# Placa_final_para_testes.net
KiCad netlist of a schematic drawn in EAGLE
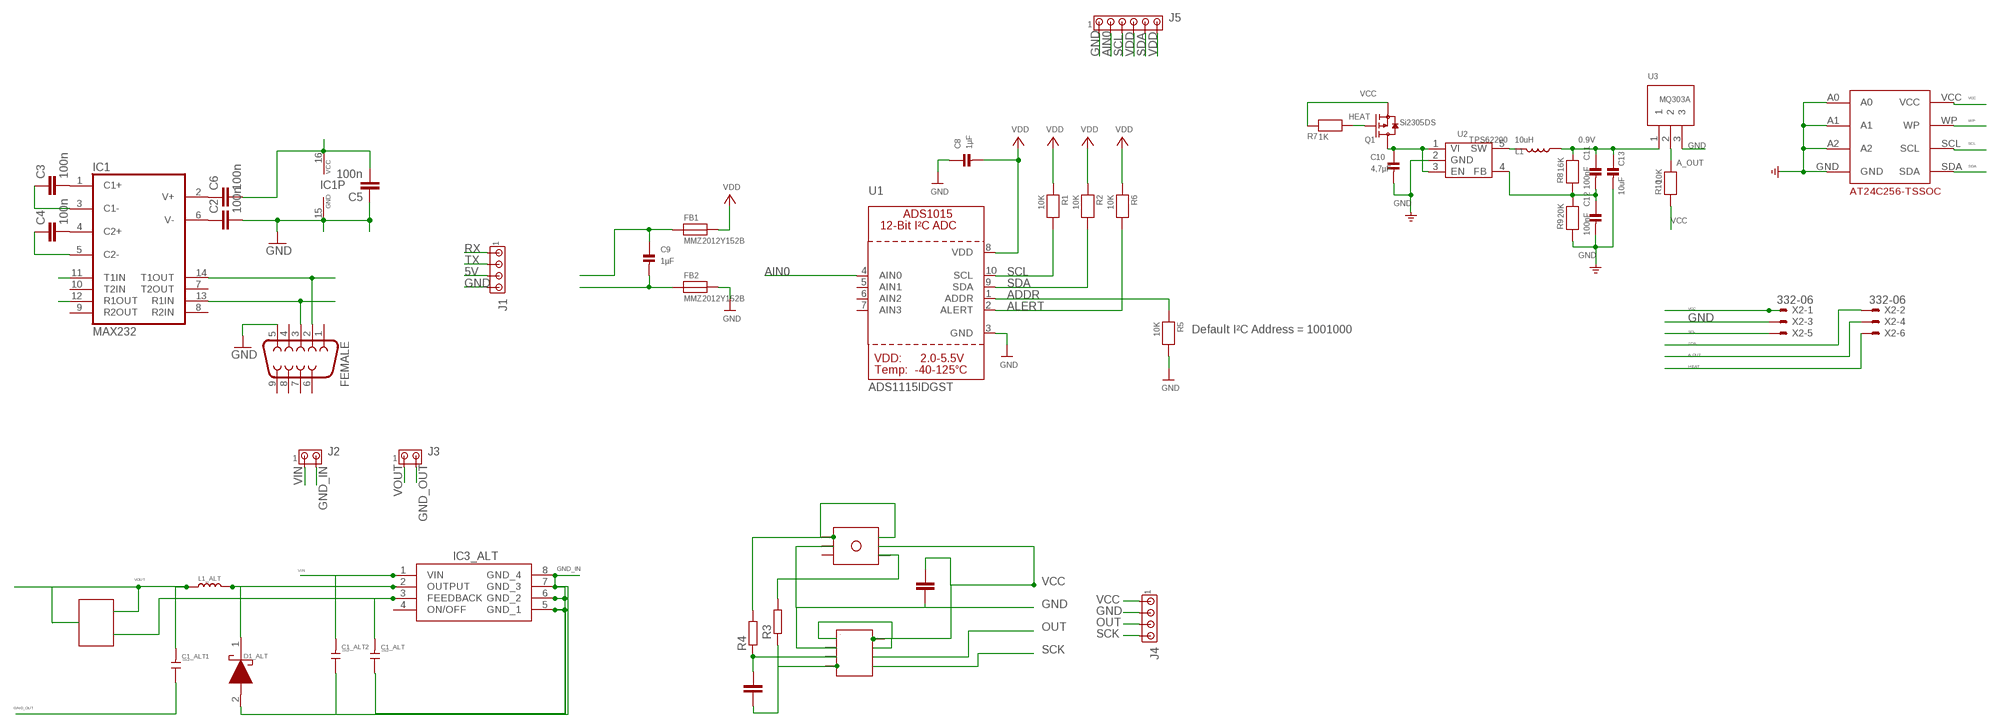
[diagram p0: schematic, sheet 1]

(export (version "E")
  (design (tool "Eeschema 10.0.6"))
  (components
    (comp (ref "C1")
      (value "100n")
      (footprint "eagle-import:C0805")
      (libsource (lib "eagle-import") (part "C-EUC0805"))
    )
    (comp (ref "C1_ALT")
      (value "105uF")
      (footprint "eagle-import:C0805")
      (libsource (lib "eagle-import") (part "C-0805"))
    )
    (comp (ref "C1_ALT1")
      (value "105uF")
      (footprint "eagle-import:C0805")
      (libsource (lib "eagle-import") (part "C-0805"))
    )
    (comp (ref "C1_ALT2")
      (value "105uF")
      (footprint "eagle-import:C0805")
      (libsource (lib "eagle-import") (part "C-0805"))
    )
    (comp (ref "C2")
      (value "100n")
      (footprint "eagle-import:C0805")
      (libsource (lib "eagle-import") (part "C-EUC0805"))
    )
    (comp (ref "C3")
      (value "100n")
      (footprint "eagle-import:C0805")
      (libsource (lib "eagle-import") (part "C-EUC0805"))
    )
    (comp (ref "C4")
      (value "100n")
      (footprint "eagle-import:C0805")
      (libsource (lib "eagle-import") (part "C-EUC0805"))
    )
    (comp (ref "C5")
      (value "100n")
      (footprint "eagle-import:C0805")
      (libsource (lib "eagle-import") (part "C-EUC0805"))
    )
    (comp (ref "C6")
      (value "100n")
      (footprint "eagle-import:C0805")
      (libsource (lib "eagle-import") (part "C-EUC0805"))
    )
    (comp (ref "C7")
      (value "100n")
      (footprint "eagle-import:C0805")
      (libsource (lib "eagle-import") (part "C-EUC0805"))
    )
    (comp (ref "C8")
      (value "1µF")
      (footprint "eagle-import:0805")
      (libsource (lib "eagle-import") (part "CAP_CERAMIC0805"))
    )
    (comp (ref "C9")
      (value "1µF")
      (footprint "eagle-import:0805")
      (libsource (lib "eagle-import") (part "CAP_CERAMIC0805"))
    )
    (comp (ref "C10")
      (value "4,7µF")
      (footprint "eagle-import:0805")
      (libsource (lib "eagle-import") (part "CAP_CERAMIC0805"))
    )
    (comp (ref "C11")
      (value "100nF")
      (footprint "eagle-import:0805")
      (libsource (lib "eagle-import") (part "CAP_CERAMIC0805"))
    )
    (comp (ref "C12")
      (value "100nF")
      (footprint "eagle-import:0805")
      (libsource (lib "eagle-import") (part "CAP_CERAMIC0805"))
    )
    (comp (ref "C13")
      (value "10uF")
      (footprint "eagle-import:0805")
      (libsource (lib "eagle-import") (part "CAP_CERAMIC0805"))
    )
    (comp (ref "D1_ALT")
      (value "1N5819HW1-7-F")
      (footprint "eagle-import:SODFL3518X115N")
      (fields (field (name "MOUSER_PART_NUMBER") "621-1N5819HW1-7-F"))
      (libsource (lib "eagle-import") (part "1N5819HW1-7-F"))
    )
    (comp (ref "FB1")
      (value "MMZ2012Y152B")
      (footprint "eagle-import:0805")
      (libsource (lib "eagle-import") (part "FERRITE0805"))
    )
    (comp (ref "FB2")
      (value "MMZ2012Y152B")
      (footprint "eagle-import:0805")
      (libsource (lib "eagle-import") (part "FERRITE0805"))
    )
    (comp (ref "FEMALE")
      (value "F09H")
      (footprint "eagle-import:F09H")
      (libsource (lib "eagle-import") (part "F09H"))
    )
    (comp (ref "IC1")
      (value "MAX232")
      (footprint "eagle-import:SO16")
      (libsource (lib "eagle-import") (part "MAX232ECWES"))
    )
    (comp (ref "IC3_ALT")
      (value "XL1509-3.3E1")
      (footprint "eagle-import:SOIC127P600X175-8N")
      (libsource (lib "eagle-import") (part "XL1509-3.3E1"))
    )
    (comp (ref "J1")
      (value "MTA04-156")
      (footprint "eagle-import:1X4MTA")
      (libsource (lib "eagle-import") (part "MTA04-156"))
    )
    (comp (ref "J2")
      (value "MTA02-156")
      (footprint "eagle-import:1X2MTA")
      (libsource (lib "eagle-import") (part "MTA02-156"))
    )
    (comp (ref "J3")
      (value "MTA02-156")
      (footprint "eagle-import:1X2MTA")
      (libsource (lib "eagle-import") (part "MTA02-156"))
    )
    (comp (ref "J4")
      (value "MTA04-100")
      (footprint "eagle-import:10X04MTA")
      (libsource (lib "eagle-import") (part "MTA04-100"))
    )
    (comp (ref "J5")
      (value "MTA06-156")
      (footprint "eagle-import:1X6MTA")
      (libsource (lib "eagle-import") (part "MTA06-156"))
    )
    (comp (ref "L1")
      (value "10uH")
      (footprint "eagle-import:PIO73")
      (libsource (lib "eagle-import") (part "L'PIO73'"))
    )
    (comp (ref "L1_ALT")
      (value "47uH")
      (footprint "eagle-import:PIO73")
      (libsource (lib "eagle-import") (part "discrete_211_L'PIO73'"))
    )
    (comp (ref "Q1")
      (value "Si2305DS")
      (footprint "eagle-import:SOT23")
      (libsource (lib "eagle-import") (part "MOSFET-P'SI2323CDS/SI2305DS{lt}BR{gt}'"))
    )
    (comp (ref "R1")
      (value "10K")
      (footprint "eagle-import:0805")
      (libsource (lib "eagle-import") (part "RESISTOR0805"))
    )
    (comp (ref "R2")
      (value "10K")
      (footprint "eagle-import:0805")
      (libsource (lib "eagle-import") (part "RESISTOR0805"))
    )
    (comp (ref "R3")
      (value "R-EU_R0805")
      (footprint "eagle-import:R0805")
      (libsource (lib "eagle-import") (part "R-EU_R0805"))
    )
    (comp (ref "R4")
      (value "R-EU_R0805")
      (footprint "eagle-import:R0805")
      (libsource (lib "eagle-import") (part "R-EU_R0805"))
    )
    (comp (ref "R5")
      (value "10K")
      (footprint "eagle-import:0805")
      (libsource (lib "eagle-import") (part "RESISTOR0805"))
    )
    (comp (ref "R6")
      (value "10K")
      (footprint "eagle-import:0805")
      (libsource (lib "eagle-import") (part "RESISTOR0805"))
    )
    (comp (ref "R7")
      (value "1K")
      (footprint "eagle-import:0805")
      (libsource (lib "eagle-import") (part "RESISTOR0805"))
    )
    (comp (ref "R8")
      (value "16K")
      (footprint "eagle-import:0805")
      (libsource (lib "eagle-import") (part "RESISTOR0805"))
    )
    (comp (ref "R9")
      (value "20K")
      (footprint "eagle-import:0805")
      (libsource (lib "eagle-import") (part "RESISTOR0805"))
    )
    (comp (ref "R10")
      (value "10K")
      (footprint "eagle-import:0805")
      (libsource (lib "eagle-import") (part "RESISTOR0805"))
    )
    (comp (ref "U$1")
      (value "TRIMPOT")
      (footprint "eagle-import:TRIMPOT")
      (libsource (lib "eagle-import") (part "TRIMPOT"))
    )
    (comp (ref "U$2")
      (value "HX710B")
      (footprint "eagle-import:HX710B")
      (libsource (lib "eagle-import") (part "HX710B"))
    )
    (comp (ref "U$3")
      (value "PRESSURE")
      (footprint "eagle-import:PRESSURE")
      (libsource (lib "eagle-import") (part "PRESSURE"))
    )
    (comp (ref "U$15")
      (value "DECADE-AT24C256-10TI-2.7")
      (footprint "eagle-import:DECADE-AT24CXX")
      (libsource (lib "eagle-import") (part "DECADE-AT24C256-10TI-2.7"))
    )
    (comp (ref "U1")
      (value "ADS1115IDGST")
      (footprint "eagle-import:MSOP10")
      (libsource (lib "eagle-import") (part "ADC_ADS1015"))
    )
    (comp (ref "U2")
      (value "TPS62200")
      (footprint "eagle-import:SOT23-5")
      (libsource (lib "eagle-import") (part "TPS62200DBV"))
    )
    (comp (ref "U3")
      (value "MQ303A")
      (footprint "eagle-import:MQ303A")
      (libsource (lib "eagle-import") (part "MQ303A"))
    )
    (comp (ref "X2")
      (value "332-06")
      (footprint "eagle-import:332-06")
      (libsource (lib "eagle-import") (part "332-06"))
    )
  )
  (nets
    (net (code "1") (name "/0.9V") (class "Default")
      (node (ref "C11") (pin "1") (pinfunction "P$1_1") (pintype "passive"))
      (node (ref "C13") (pin "1") (pinfunction "P$1_1") (pintype "passive"))
      (node (ref "L1") (pin "2") (pinfunction "2_2") (pintype "passive"))
      (node (ref "R8") (pin "2") (pinfunction "2_2") (pintype "passive"))
      (node (ref "U3") (pin "1") (pinfunction "1_1") (pintype "bidirectional"))
    )
    (net (code "2") (name "/5V") (class "Default")
      (node (ref "C5") (pin "2") (pinfunction "2_2") (pintype "passive"))
      (node (ref "C6") (pin "2") (pinfunction "2_2") (pintype "passive"))
      (node (ref "IC1") (pin "16") (pinfunction "VCC_16") (pintype "power_in"))
      (node (ref "J1") (pin "3") (pinfunction "3_3") (pintype "passive"))
    )
    (net (code "3") (name "/ADDR") (class "Default")
      (node (ref "R5") (pin "1") (pinfunction "1_1") (pintype "passive"))
      (node (ref "U1") (pin "1") (pinfunction "ADDR_1") (pintype "bidirectional"))
    )
    (net (code "4") (name "/AIN0") (class "Default")
      (node (ref "J5") (pin "2") (pinfunction "2_2") (pintype "passive"))
      (node (ref "U1") (pin "4") (pinfunction "AIN0_4") (pintype "bidirectional"))
    )
    (net (code "5") (name "/ALERT") (class "Default")
      (node (ref "R6") (pin "2") (pinfunction "2_2") (pintype "passive"))
      (node (ref "U1") (pin "2") (pinfunction "ALERT_2") (pintype "bidirectional"))
    )
    (net (code "6") (name "/A_OUT") (class "Default")
      (node (ref "R10") (pin "2") (pinfunction "2_2") (pintype "passive"))
      (node (ref "U3") (pin "2") (pinfunction "2_2") (pintype "bidirectional"))
      (node (ref "X2") (pin "4") (pinfunction "S_4") (pintype "passive"))
    )
    (net (code "7") (name "/GND_IN") (class "Default")
      (node (ref "C1_ALT") (pin "1") (pinfunction "1_1") (pintype "passive"))
      (node (ref "C1_ALT2") (pin "1") (pinfunction "1_1") (pintype "passive"))
      (node (ref "D1_ALT") (pin "2") (pinfunction "A_2") (pintype "bidirectional"))
      (node (ref "IC3_ALT") (pin "5") (pinfunction "GND_1_5") (pintype "bidirectional"))
      (node (ref "IC3_ALT") (pin "6") (pinfunction "GND_2_6") (pintype "bidirectional"))
      (node (ref "IC3_ALT") (pin "7") (pinfunction "GND_3_7") (pintype "bidirectional"))
      (node (ref "IC3_ALT") (pin "8") (pinfunction "GND_4_8") (pintype "bidirectional"))
      (node (ref "J2") (pin "2") (pinfunction "2_2") (pintype "passive"))
    )
    (net (code "8") (name "/GND_OUT") (class "Default")
      (node (ref "C1_ALT1") (pin "1") (pinfunction "1_1") (pintype "passive"))
      (node (ref "J3") (pin "2") (pinfunction "2_2") (pintype "passive"))
    )
    (net (code "9") (name "/HEAT") (class "Default")
      (node (ref "Q1") (pin "1") (pinfunction "G_1") (pintype "passive"))
      (node (ref "R7") (pin "2") (pinfunction "2_2") (pintype "passive"))
      (node (ref "X2") (pin "6") (pinfunction "S_6") (pintype "passive"))
    )
    (net (code "10") (name "/OUT") (class "Default")
      (node (ref "J4") (pin "3") (pinfunction "3_3") (pintype "passive"))
      (node (ref "U$2") (pin "DOUT") (pinfunction "DOUT_DOUT") (pintype "bidirectional"))
    )
    (net (code "11") (name "/RX") (class "Default")
      (node (ref "IC1") (pin "12") (pinfunction "R1OUT_12") (pintype "output"))
      (node (ref "J1") (pin "1") (pinfunction "1_1") (pintype "passive"))
    )
    (net (code "12") (name "/SCK") (class "Default")
      (node (ref "J4") (pin "4") (pinfunction "4_4") (pintype "passive"))
      (node (ref "U$2") (pin "SCK") (pinfunction "SCK_SCK") (pintype "bidirectional"))
    )
    (net (code "13") (name "/SCL") (class "Default")
      (node (ref "J5") (pin "3") (pinfunction "3_3") (pintype "passive"))
      (node (ref "R1") (pin "2") (pinfunction "2_2") (pintype "passive"))
      (node (ref "U$15") (pin "SCL") (pinfunction "SCL_SCL") (pintype "bidirectional"))
      (node (ref "U1") (pin "10") (pinfunction "SCL_10") (pintype "bidirectional"))
      (node (ref "X2") (pin "5") (pinfunction "S_5") (pintype "passive"))
    )
    (net (code "14") (name "/SDA") (class "Default")
      (node (ref "J5") (pin "5") (pinfunction "5_5") (pintype "passive"))
      (node (ref "R2") (pin "2") (pinfunction "2_2") (pintype "passive"))
      (node (ref "U$15") (pin "SDA") (pinfunction "SDA_SDA") (pintype "bidirectional"))
      (node (ref "U1") (pin "9") (pinfunction "SDA_9") (pintype "bidirectional"))
      (node (ref "X2") (pin "2") (pinfunction "S_2") (pintype "passive"))
    )
    (net (code "15") (name "/TX") (class "Default")
      (node (ref "IC1") (pin "11") (pinfunction "T1IN_11") (pintype "input"))
      (node (ref "J1") (pin "2") (pinfunction "2_2") (pintype "passive"))
    )
    (net (code "16") (name "/VCC") (class "Default")
      (node (ref "C7") (pin "1") (pinfunction "1_1") (pintype "passive"))
      (node (ref "J4") (pin "1") (pinfunction "1_1") (pintype "passive"))
      (node (ref "Q1") (pin "2") (pinfunction "S_2") (pintype "passive"))
      (node (ref "R10") (pin "1") (pinfunction "1_1") (pintype "passive"))
      (node (ref "R7") (pin "1") (pinfunction "1_1") (pintype "passive"))
      (node (ref "U$15") (pin "VCC") (pinfunction "VCC_VCC") (pintype "bidirectional"))
      (node (ref "U$2") (pin "AVDD") (pinfunction "AVDD_AVDD") (pintype "bidirectional"))
      (node (ref "U$2") (pin "DVDD") (pinfunction "DVDD_DVDD") (pintype "bidirectional"))
      (node (ref "U$2") (pin "VREF") (pinfunction "VREF_VREF") (pintype "bidirectional"))
      (node (ref "U$3") (pin "5") (pinfunction "5_5") (pintype "bidirectional"))
      (node (ref "X2") (pin "1") (pinfunction "S_1") (pintype "passive"))
    )
    (net (code "17") (name "/VIN") (class "Default")
      (node (ref "C1_ALT2") (pin "2") (pinfunction "2_2") (pintype "passive"))
      (node (ref "IC3_ALT") (pin "1") (pinfunction "VIN_1") (pintype "bidirectional"))
      (node (ref "J2") (pin "1") (pinfunction "1_1") (pintype "passive"))
    )
    (net (code "18") (name "/VOUT") (class "Default")
      (node (ref "C1_ALT1") (pin "2") (pinfunction "2_2") (pintype "passive"))
      (node (ref "J3") (pin "1") (pinfunction "1_1") (pintype "passive"))
      (node (ref "L1_ALT") (pin "2") (pinfunction "2_2") (pintype "passive"))
      (node (ref "U$1") (pin "VCC1") (pinfunction "VCC1_VCC1") (pintype "bidirectional"))
      (node (ref "U$1") (pin "VCC2") (pinfunction "VCC2_VCC2") (pintype "bidirectional"))
    )
    (net (code "19") (name "/WP") (class "Default")
      (node (ref "U$15") (pin "WP") (pinfunction "WP_WP") (pintype "bidirectional"))
    )
    (net (code "20") (name "GND") (class "Default")
      (node (ref "C10") (pin "2") (pinfunction "P$2_2") (pintype "passive"))
      (node (ref "C12") (pin "2") (pinfunction "P$2_2") (pintype "passive"))
      (node (ref "C13") (pin "2") (pinfunction "P$2_2") (pintype "passive"))
      (node (ref "C2") (pin "2") (pinfunction "2_2") (pintype "passive"))
      (node (ref "C5") (pin "1") (pinfunction "1_1") (pintype "passive"))
      (node (ref "C7") (pin "2") (pinfunction "2_2") (pintype "passive"))
      (node (ref "C8") (pin "1") (pinfunction "P$1_1") (pintype "passive"))
      (node (ref "FB2") (pin "2") (pinfunction "P$2_2") (pintype "bidirectional"))
      (node (ref "FEMALE") (pin "5") (pinfunction "5_5") (pintype "passive"))
      (node (ref "IC1") (pin "15") (pinfunction "GND_15") (pintype "power_in"))
      (node (ref "J1") (pin "4") (pinfunction "4_4") (pintype "passive"))
      (node (ref "J4") (pin "2") (pinfunction "2_2") (pintype "passive"))
      (node (ref "J5") (pin "1") (pinfunction "1_1") (pintype "passive"))
      (node (ref "R5") (pin "2") (pinfunction "2_2") (pintype "passive"))
      (node (ref "R9") (pin "1") (pinfunction "1_1") (pintype "passive"))
      (node (ref "U$15") (pin "A0") (pinfunction "A0_A0") (pintype "bidirectional"))
      (node (ref "U$15") (pin "A1") (pinfunction "A1_A1") (pintype "bidirectional"))
      (node (ref "U$15") (pin "A2") (pinfunction "A2_A2") (pintype "bidirectional"))
      (node (ref "U$15") (pin "GND") (pinfunction "GND_GND") (pintype "bidirectional"))
      (node (ref "U$2") (pin "AGND") (pinfunction "AGND_AGND") (pintype "bidirectional"))
      (node (ref "U$3") (pin "2") (pinfunction "2_2") (pintype "bidirectional"))
      (node (ref "U1") (pin "3") (pinfunction "GND_3") (pintype "bidirectional"))
      (node (ref "U2") (pin "2") (pinfunction "GND_2") (pintype "power_in"))
      (node (ref "U3") (pin "3") (pinfunction "3_3") (pintype "bidirectional"))
      (node (ref "X2") (pin "3") (pinfunction "S_3") (pintype "passive"))
    )
    (net (code "21") (name "Net-(C1-Pad1)") (class "Default")
      (node (ref "C1") (pin "1") (pinfunction "1_1") (pintype "passive"))
      (node (ref "R3") (pin "1") (pinfunction "1_1") (pintype "passive"))
      (node (ref "U$2") (pin "INP") (pinfunction "INP_INP") (pintype "bidirectional"))
    )
    (net (code "22") (name "Net-(C1-Pad2)") (class "Default")
      (node (ref "C1") (pin "2") (pinfunction "2_2") (pintype "passive"))
      (node (ref "R4") (pin "1") (pinfunction "1_1") (pintype "passive"))
      (node (ref "U$2") (pin "INN") (pinfunction "INN_INN") (pintype "bidirectional"))
    )
    (net (code "23") (name "Net-(C9-P$1)") (class "Default")
      (node (ref "C9") (pin "1") (pinfunction "P$1_1") (pintype "passive"))
      (node (ref "FB1") (pin "1") (pinfunction "P$1_1") (pintype "bidirectional"))
    )
    (net (code "24") (name "Net-(C9-P$2)") (class "Default")
      (node (ref "C9") (pin "2") (pinfunction "P$2_2") (pintype "passive"))
      (node (ref "FB2") (pin "1") (pinfunction "P$1_1") (pintype "bidirectional"))
    )
    (net (code "25") (name "Net-(C10-P$1)") (class "Default")
      (node (ref "C10") (pin "1") (pinfunction "P$1_1") (pintype "passive"))
      (node (ref "Q1") (pin "3") (pinfunction "D_3") (pintype "passive"))
      (node (ref "U2") (pin "1") (pinfunction "VI_1") (pintype "input"))
      (node (ref "U2") (pin "3") (pinfunction "EN_3") (pintype "input"))
    )
    (net (code "26") (name "Net-(C11-P$2)") (class "Default")
      (node (ref "C11") (pin "2") (pinfunction "P$2_2") (pintype "passive"))
      (node (ref "C12") (pin "1") (pinfunction "P$1_1") (pintype "passive"))
      (node (ref "R8") (pin "1") (pinfunction "1_1") (pintype "passive"))
      (node (ref "R9") (pin "2") (pinfunction "2_2") (pintype "passive"))
      (node (ref "U2") (pin "4") (pinfunction "FB_4") (pintype "input"))
    )
    (net (code "27") (name "Net-(D1_ALT-K)") (class "Default")
      (node (ref "D1_ALT") (pin "1") (pinfunction "K_1") (pintype "bidirectional"))
      (node (ref "IC3_ALT") (pin "2") (pinfunction "OUTPUT_2") (pintype "bidirectional"))
      (node (ref "L1_ALT") (pin "1") (pinfunction "1_1") (pintype "passive"))
    )
    (net (code "28") (name "Net-(IC1A-C1+)") (class "Default")
      (node (ref "C3") (pin "2") (pinfunction "2_2") (pintype "passive"))
      (node (ref "IC1") (pin "1") (pinfunction "C1+_1") (pintype "bidirectional"))
    )
    (net (code "29") (name "Net-(IC1A-C1-)") (class "Default")
      (node (ref "C3") (pin "1") (pinfunction "1_1") (pintype "passive"))
      (node (ref "IC1") (pin "3") (pinfunction "C1-_3") (pintype "bidirectional"))
    )
    (net (code "30") (name "Net-(IC1A-C2+)") (class "Default")
      (node (ref "C4") (pin "2") (pinfunction "2_2") (pintype "passive"))
      (node (ref "IC1") (pin "4") (pinfunction "C2+_4") (pintype "bidirectional"))
    )
    (net (code "31") (name "Net-(IC1A-C2-)") (class "Default")
      (node (ref "C4") (pin "1") (pinfunction "1_1") (pintype "passive"))
      (node (ref "IC1") (pin "5") (pinfunction "C2-_5") (pintype "bidirectional"))
    )
    (net (code "32") (name "Net-(IC1A-R1IN)") (class "Default")
      (node (ref "FEMALE") (pin "3") (pinfunction "3_3") (pintype "passive"))
      (node (ref "IC1") (pin "13") (pinfunction "R1IN_13") (pintype "input"))
    )
    (net (code "33") (name "Net-(IC1A-T1OUT)") (class "Default")
      (node (ref "FEMALE") (pin "2") (pinfunction "2_2") (pintype "passive"))
      (node (ref "IC1") (pin "14") (pinfunction "T1OUT_14") (pintype "output"))
    )
    (net (code "34") (name "Net-(IC1A-V+)") (class "Default")
      (node (ref "C6") (pin "1") (pinfunction "1_1") (pintype "passive"))
      (node (ref "IC1") (pin "2") (pinfunction "V+_2") (pintype "bidirectional"))
    )
    (net (code "35") (name "Net-(IC1A-V-)") (class "Default")
      (node (ref "C2") (pin "1") (pinfunction "1_1") (pintype "passive"))
      (node (ref "IC1") (pin "6") (pinfunction "V-_6") (pintype "bidirectional"))
    )
    (net (code "36") (name "Net-(IC3_ALT-FEEDBACK)") (class "Default")
      (node (ref "C1_ALT") (pin "2") (pinfunction "2_2") (pintype "passive"))
      (node (ref "IC3_ALT") (pin "3") (pinfunction "FEEDBACK_3") (pintype "bidirectional"))
      (node (ref "U$1") (pin "OUT") (pinfunction "OUT_OUT") (pintype "bidirectional"))
    )
    (net (code "37") (name "Net-(R3-Pad2)") (class "Default")
      (node (ref "R3") (pin "2") (pinfunction "2_2") (pintype "passive"))
      (node (ref "U$3") (pin "4") (pinfunction "4_4") (pintype "bidirectional"))
    )
    (net (code "38") (name "Net-(R4-Pad2)") (class "Default")
      (node (ref "R4") (pin "2") (pinfunction "2_2") (pintype "passive"))
      (node (ref "U$3") (pin "1") (pinfunction "1_1") (pintype "bidirectional"))
      (node (ref "U$3") (pin "6") (pinfunction "6_6") (pintype "bidirectional"))
    )
    (net (code "39") (name "Net-(U2-SW)") (class "Default")
      (node (ref "L1") (pin "1") (pinfunction "1_1") (pintype "passive"))
      (node (ref "U2") (pin "5") (pinfunction "SW_5") (pintype "bidirectional"))
    )
    (net (code "40") (name "VDD") (class "Default")
      (node (ref "C8") (pin "2") (pinfunction "P$2_2") (pintype "passive"))
      (node (ref "FB1") (pin "2") (pinfunction "P$2_2") (pintype "bidirectional"))
      (node (ref "J5") (pin "4") (pinfunction "4_4") (pintype "passive"))
      (node (ref "J5") (pin "6") (pinfunction "6_6") (pintype "passive"))
      (node (ref "R1") (pin "1") (pinfunction "1_1") (pintype "passive"))
      (node (ref "R2") (pin "1") (pinfunction "1_1") (pintype "passive"))
      (node (ref "R6") (pin "1") (pinfunction "1_1") (pintype "passive"))
      (node (ref "U1") (pin "8") (pinfunction "VDD_8") (pintype "bidirectional"))
    )
    (net (code "41") (name "unconnected-(FEMALE-Pad1)") (class "Default")
      (node (ref "FEMALE") (pin "1") (pinfunction "1_1") (pintype "passive"))
    )
    (net (code "42") (name "unconnected-(FEMALE-Pad4)") (class "Default")
      (node (ref "FEMALE") (pin "4") (pinfunction "4_4") (pintype "passive"))
    )
    (net (code "43") (name "unconnected-(FEMALE-Pad6)") (class "Default")
      (node (ref "FEMALE") (pin "6") (pinfunction "6_6") (pintype "passive"))
    )
    (net (code "44") (name "unconnected-(FEMALE-Pad7)") (class "Default")
      (node (ref "FEMALE") (pin "7") (pinfunction "7_7") (pintype "passive"))
    )
    (net (code "45") (name "unconnected-(FEMALE-Pad8)") (class "Default")
      (node (ref "FEMALE") (pin "8") (pinfunction "8_8") (pintype "passive"))
    )
    (net (code "46") (name "unconnected-(FEMALE-Pad9)") (class "Default")
      (node (ref "FEMALE") (pin "9") (pinfunction "9_9") (pintype "passive"))
    )
    (net (code "47") (name "unconnected-(IC1A-R2IN-Pad8)") (class "Default")
      (node (ref "IC1") (pin "8") (pinfunction "R2IN_8") (pintype "input"))
    )
    (net (code "48") (name "unconnected-(IC1A-R2OUT-Pad9)") (class "Default")
      (node (ref "IC1") (pin "9") (pinfunction "R2OUT_9") (pintype "output"))
    )
    (net (code "49") (name "unconnected-(IC1A-T2IN-Pad10)") (class "Default")
      (node (ref "IC1") (pin "10") (pinfunction "T2IN_10") (pintype "input"))
    )
    (net (code "50") (name "unconnected-(IC1A-T2OUT-Pad7)") (class "Default")
      (node (ref "IC1") (pin "7") (pinfunction "T2OUT_7") (pintype "output"))
    )
    (net (code "51") (name "unconnected-(IC3_ALT-ON{slash}OFF-Pad4)") (class "Default")
      (node (ref "IC3_ALT") (pin "4") (pinfunction "ON/OFF_4") (pintype "bidirectional"))
    )
    (net (code "52") (name "unconnected-(U$3-Pad3)") (class "Default")
      (node (ref "U$3") (pin "3") (pinfunction "3_3") (pintype "bidirectional"))
    )
    (net (code "53") (name "unconnected-(U1-AIN1-Pad5)") (class "Default")
      (node (ref "U1") (pin "5") (pinfunction "AIN1_5") (pintype "bidirectional"))
    )
    (net (code "54") (name "unconnected-(U1-AIN2-Pad6)") (class "Default")
      (node (ref "U1") (pin "6") (pinfunction "AIN2_6") (pintype "bidirectional"))
    )
    (net (code "55") (name "unconnected-(U1-AIN3-Pad7)") (class "Default")
      (node (ref "U1") (pin "7") (pinfunction "AIN3_7") (pintype "bidirectional"))
    )
  )
)
